# osi-power_dc_rev_0.net
KiCad netlist of a schematic drawn in EAGLE
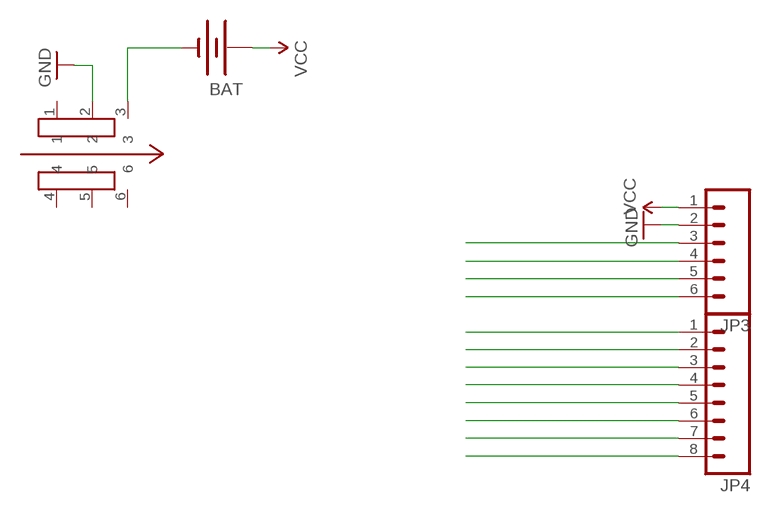
[diagram p0: schematic, sheet 1]

(export (version "E")
  (design (tool "Eeschema 10.0.6"))
  (components
    (comp (ref "BAT")
      (value "BATTERY20PTH")
      (footprint "eagle-import:BATTCOM_20MM_PTH")
      (libsource (lib "eagle-import") (part "BATTERY20PTH"))
    )
    (comp (ref "JP3")
      (value "M06SIP")
      (footprint "eagle-import:1X06")
      (libsource (lib "eagle-import") (part "M06SIP"))
    )
    (comp (ref "JP4")
      (value "M081X08")
      (footprint "eagle-import:1X08")
      (libsource (lib "eagle-import") (part "M081X08"))
    )
    (comp (ref "U$1")
      (value "SWITCH")
      (footprint "eagle-import:SWITCH")
      (libsource (lib "eagle-import") (part "SWITCH"))
    )
  )
  (nets
    (net (code "1") (name "GND") (class "Default")
      (node (ref "JP3") (pin "2") (pinfunction "2_2") (pintype "passive"))
      (node (ref "U$1") (pin "2") (pinfunction "2_2") (pintype "bidirectional"))
    )
    (net (code "2") (name "Net-(BAT--)") (class "Default")
      (node (ref "BAT") (pin "2") (pinfunction "-_2") (pintype "power_in"))
      (node (ref "U$1") (pin "3") (pinfunction "3_3") (pintype "bidirectional"))
    )
    (net (code "3") (name "VCC") (class "Default")
      (node (ref "BAT") (pin "1") (pinfunction "+_1") (pintype "power_in"))
      (node (ref "JP3") (pin "1") (pinfunction "1_1") (pintype "passive"))
    )
    (net (code "4") (name "unconnected-(JP3-Pad3)") (class "Default")
      (node (ref "JP3") (pin "3") (pinfunction "3_3") (pintype "passive"))
    )
    (net (code "5") (name "unconnected-(JP3-Pad4)") (class "Default")
      (node (ref "JP3") (pin "4") (pinfunction "4_4") (pintype "passive"))
    )
    (net (code "6") (name "unconnected-(JP3-Pad5)") (class "Default")
      (node (ref "JP3") (pin "5") (pinfunction "5_5") (pintype "passive"))
    )
    (net (code "7") (name "unconnected-(JP3-Pad6)") (class "Default")
      (node (ref "JP3") (pin "6") (pinfunction "6_6") (pintype "passive"))
    )
    (net (code "8") (name "unconnected-(JP4-Pad1)") (class "Default")
      (node (ref "JP4") (pin "1") (pinfunction "1_1") (pintype "passive"))
    )
    (net (code "9") (name "unconnected-(JP4-Pad2)") (class "Default")
      (node (ref "JP4") (pin "2") (pinfunction "2_2") (pintype "passive"))
    )
    (net (code "10") (name "unconnected-(JP4-Pad3)") (class "Default")
      (node (ref "JP4") (pin "3") (pinfunction "3_3") (pintype "passive"))
    )
    (net (code "11") (name "unconnected-(JP4-Pad4)") (class "Default")
      (node (ref "JP4") (pin "4") (pinfunction "4_4") (pintype "passive"))
    )
    (net (code "12") (name "unconnected-(JP4-Pad5)") (class "Default")
      (node (ref "JP4") (pin "5") (pinfunction "5_5") (pintype "passive"))
    )
    (net (code "13") (name "unconnected-(JP4-Pad6)") (class "Default")
      (node (ref "JP4") (pin "6") (pinfunction "6_6") (pintype "passive"))
    )
    (net (code "14") (name "unconnected-(JP4-Pad7)") (class "Default")
      (node (ref "JP4") (pin "7") (pinfunction "7_7") (pintype "passive"))
    )
    (net (code "15") (name "unconnected-(JP4-Pad8)") (class "Default")
      (node (ref "JP4") (pin "8") (pinfunction "8_8") (pintype "passive"))
    )
    (net (code "16") (name "unconnected-(U$1-Pad1)") (class "Default")
      (node (ref "U$1") (pin "1") (pinfunction "1_1") (pintype "bidirectional"))
    )
    (net (code "17") (name "unconnected-(U$1-Pad4)") (class "Default")
      (node (ref "U$1") (pin "4") (pinfunction "4_4") (pintype "bidirectional"))
    )
    (net (code "18") (name "unconnected-(U$1-Pad5)") (class "Default")
      (node (ref "U$1") (pin "5") (pinfunction "5_5") (pintype "bidirectional"))
    )
    (net (code "19") (name "unconnected-(U$1-Pad6)") (class "Default")
      (node (ref "U$1") (pin "6") (pinfunction "6_6") (pintype "bidirectional"))
    )
  )
)
